# NE556-CD4069-Synth-Toy-CableConn.net
KiCad netlist of a schematic drawn in EAGLE
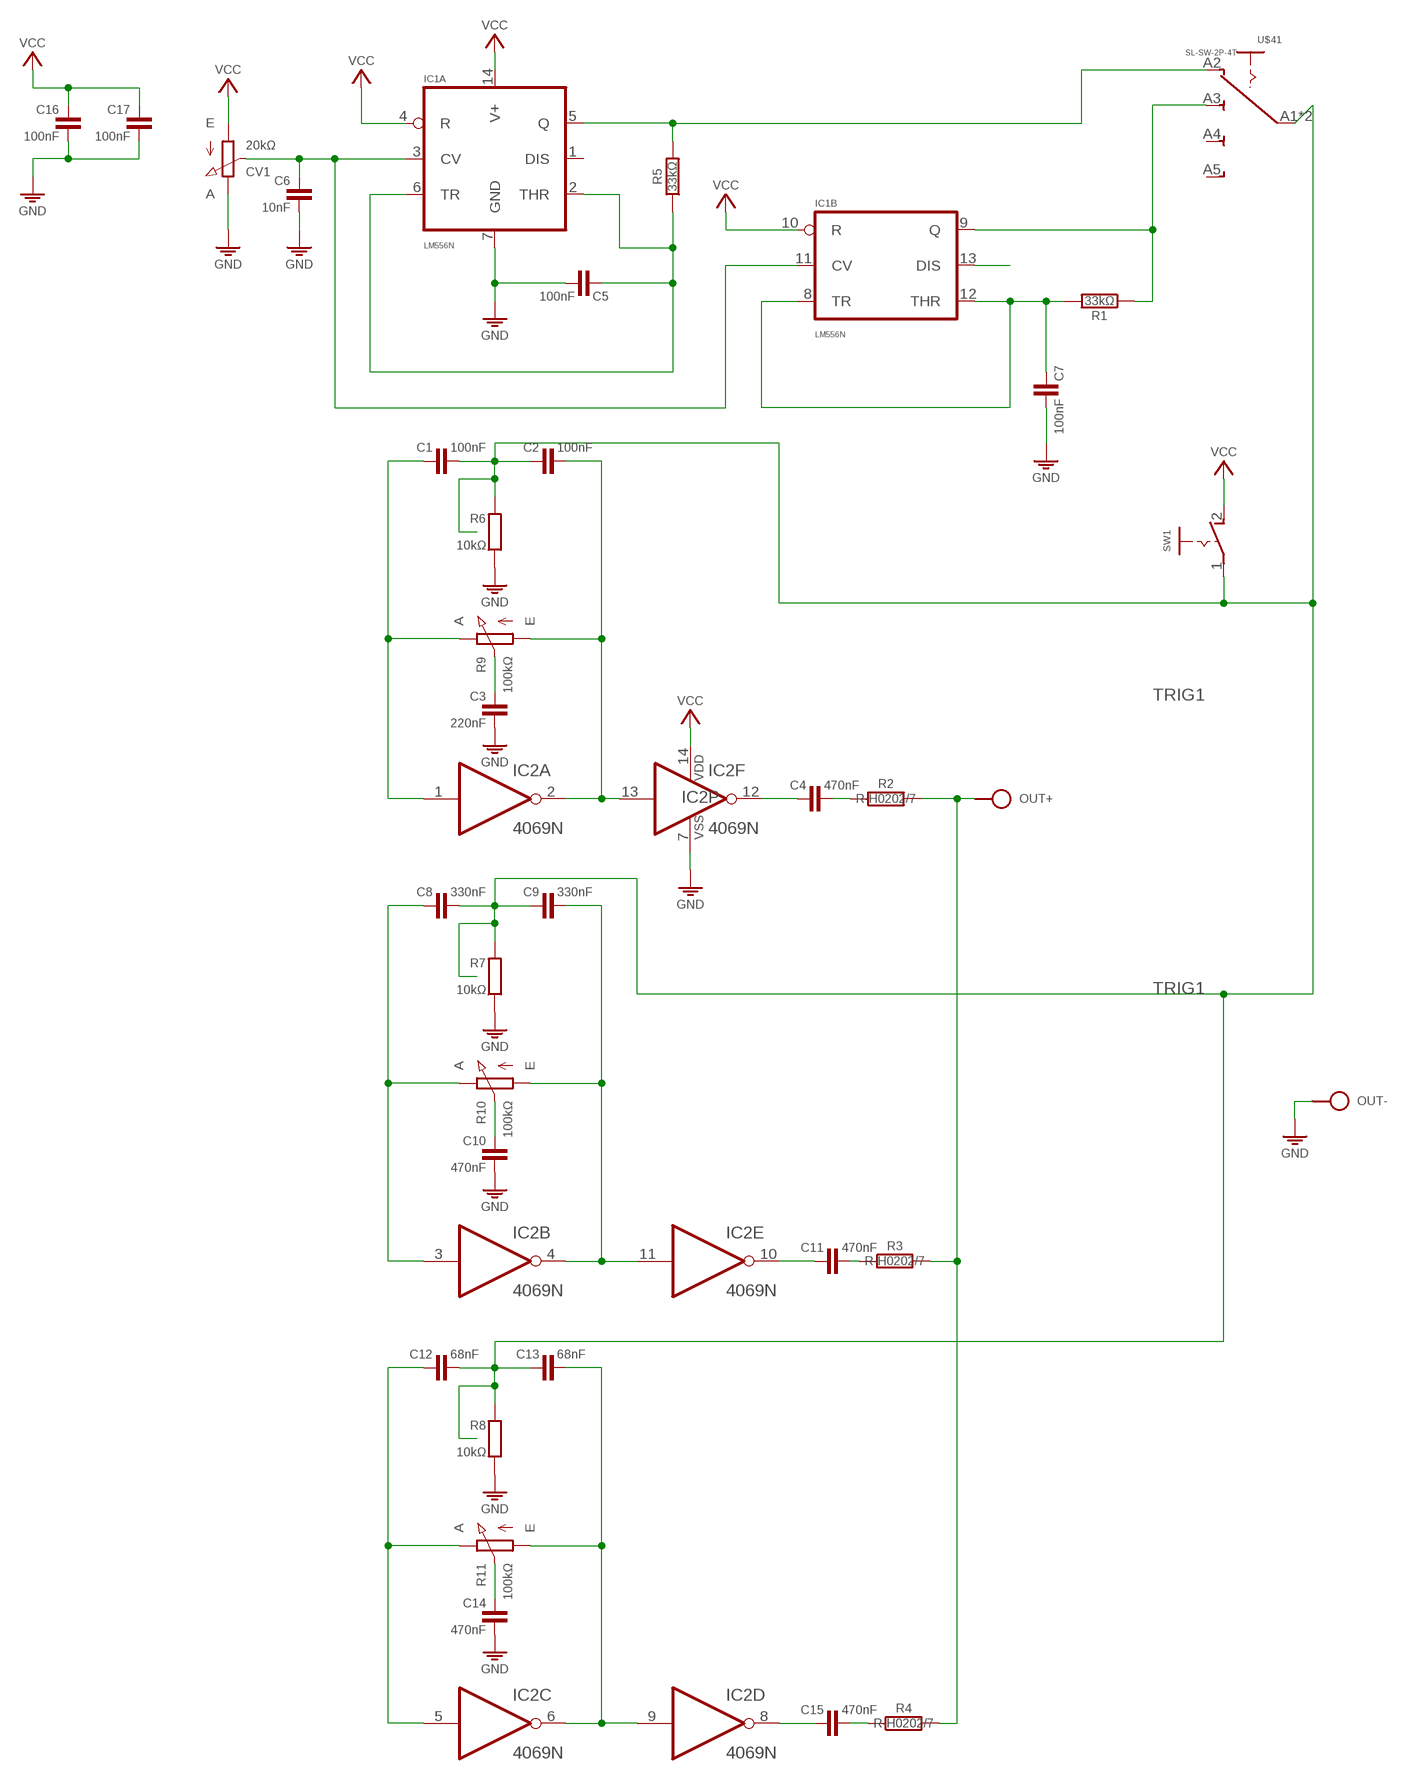
[diagram p0: schematic, sheet 1]

(export (version "E")
  (design (tool "Eeschema 10.0.6"))
  (components
    (comp (ref "C1")
      (value "100nF")
      (footprint "eagle-import:C050-020X044")
      (libsource (lib "eagle-import") (part "C-H050-020X044"))
    )
    (comp (ref "C2")
      (value "100nF")
      (footprint "eagle-import:C050-020X044")
      (libsource (lib "eagle-import") (part "C-H050-020X044"))
    )
    (comp (ref "C3")
      (value "220nF")
      (footprint "eagle-import:C050-020X044_V")
      (libsource (lib "eagle-import") (part "C050-020X044/V"))
    )
    (comp (ref "C4")
      (value "470nF")
      (footprint "eagle-import:C050-024X044")
      (libsource (lib "eagle-import") (part "C-H050-024X044"))
    )
    (comp (ref "C5")
      (value "100nF")
      (footprint "eagle-import:C050-020X044")
      (libsource (lib "eagle-import") (part "C-H050-020X044"))
    )
    (comp (ref "C6")
      (value "10nF")
      (footprint "eagle-import:C050-020X044_V")
      (libsource (lib "eagle-import") (part "C050-020X044/V"))
    )
    (comp (ref "C7")
      (value "100nF")
      (footprint "eagle-import:C050-020X044")
      (libsource (lib "eagle-import") (part "C-H050-020X044"))
    )
    (comp (ref "C8")
      (value "330nF")
      (footprint "eagle-import:C050-024X044")
      (libsource (lib "eagle-import") (part "C-H050-024X044"))
    )
    (comp (ref "C9")
      (value "330nF")
      (footprint "eagle-import:C050-024X044")
      (libsource (lib "eagle-import") (part "C-H050-024X044"))
    )
    (comp (ref "C10")
      (value "470nF")
      (footprint "eagle-import:C050-020X044_V")
      (libsource (lib "eagle-import") (part "C050-020X044/V"))
    )
    (comp (ref "C11")
      (value "470nF")
      (footprint "eagle-import:C050-024X044")
      (libsource (lib "eagle-import") (part "C-H050-024X044"))
    )
    (comp (ref "C12")
      (value "68nF")
      (footprint "eagle-import:C050-020X044")
      (libsource (lib "eagle-import") (part "C-H050-020X044"))
    )
    (comp (ref "C13")
      (value "68nF")
      (footprint "eagle-import:C050-020X044")
      (libsource (lib "eagle-import") (part "C-H050-020X044"))
    )
    (comp (ref "C14")
      (value "470nF")
      (footprint "eagle-import:C050-020X044_V")
      (libsource (lib "eagle-import") (part "C050-020X044/V"))
    )
    (comp (ref "C15")
      (value "470nF")
      (footprint "eagle-import:C050-024X044")
      (libsource (lib "eagle-import") (part "C-H050-024X044"))
    )
    (comp (ref "C16")
      (value "100nF")
      (footprint "eagle-import:C050-020X044_V")
      (libsource (lib "eagle-import") (part "C050-020X044/V"))
    )
    (comp (ref "C17")
      (value "100nF")
      (footprint "eagle-import:C050-020X044_V")
      (libsource (lib "eagle-import") (part "C050-020X044/V"))
    )
    (comp (ref "CV1")
      (value "20kΩ")
      (footprint "eagle-import:CONN-3P")
      (libsource (lib "eagle-import") (part "POT-3P"))
    )
    (comp (ref "IC1")
      (value "LM556N")
      (footprint "eagle-import:DIL14")
      (libsource (lib "eagle-import") (part "556NLM"))
    )
    (comp (ref "IC2")
      (value "4069N")
      (footprint "eagle-import:DIL14")
      (libsource (lib "eagle-import") (part "4069N"))
    )
    (comp (ref "OUT")
      (value "SPAD+--+")
      (footprint "eagle-import:SPAD-+")
      (libsource (lib "eagle-import") (part "SPAD+--+"))
    )
    (comp (ref "R1")
      (value "33kΩ")
      (footprint "eagle-import:0204_2V")
      (libsource (lib "eagle-import") (part "R-H0204/2V"))
    )
    (comp (ref "R2")
      (value "R-H0202/7")
      (footprint "eagle-import:0202_7")
      (libsource (lib "eagle-import") (part "R-H0202/7"))
    )
    (comp (ref "R3")
      (value "R-H0202/7")
      (footprint "eagle-import:0202_7")
      (libsource (lib "eagle-import") (part "R-H0202/7"))
    )
    (comp (ref "R4")
      (value "R-H0202/7")
      (footprint "eagle-import:0202_7")
      (libsource (lib "eagle-import") (part "R-H0202/7"))
    )
    (comp (ref "R5")
      (value "33kΩ")
      (footprint "eagle-import:0204_2V")
      (libsource (lib "eagle-import") (part "R-H0204/2V"))
    )
    (comp (ref "R6")
      (value "10kΩ")
      (footprint "eagle-import:0204_10-V")
      (libsource (lib "eagle-import") (part "R0204/10-V"))
    )
    (comp (ref "R7")
      (value "10kΩ")
      (footprint "eagle-import:0204_10-V")
      (libsource (lib "eagle-import") (part "R0204/10-V"))
    )
    (comp (ref "R8")
      (value "10kΩ")
      (footprint "eagle-import:0204_10-V")
      (libsource (lib "eagle-import") (part "R0204/10-V"))
    )
    (comp (ref "R9")
      (value "100kΩ")
      (footprint "eagle-import:CONN-3P")
      (libsource (lib "eagle-import") (part "POT-3P-S1"))
    )
    (comp (ref "R10")
      (value "100kΩ")
      (footprint "eagle-import:CONN-3P")
      (libsource (lib "eagle-import") (part "POT-3P-S1"))
    )
    (comp (ref "R11")
      (value "100kΩ")
      (footprint "eagle-import:CONN-3P")
      (libsource (lib "eagle-import") (part "POT-3P-S1"))
    )
    (comp (ref "S3")
      (value "VCC_GNDPWR-L")
      (footprint "eagle-import:PWR-L")
      (libsource (lib "eagle-import") (part "VCC_GNDPWR-L"))
    )
    (comp (ref "SW1")
      (value "PB-1P-1T")
      (footprint "eagle-import:PB-1P1T")
      (libsource (lib "eagle-import") (part "PB-1P-1T"))
    )
    (comp (ref "U$4")
      (value "SL-SW-2P-4T")
      (footprint "eagle-import:SLSW-2P4T-2-H")
      (libsource (lib "eagle-import") (part "SL-SW-2P-4T"))
    )
  )
  (nets
    (net (code "1") (name "/TRIG1") (class "Default")
      (node (ref "C1") (pin "2") (pinfunction "2_2") (pintype "passive"))
      (node (ref "C12") (pin "2") (pinfunction "2_2") (pintype "passive"))
      (node (ref "C13") (pin "1") (pinfunction "1_1") (pintype "passive"))
      (node (ref "C2") (pin "1") (pinfunction "1_1") (pintype "passive"))
      (node (ref "C8") (pin "2") (pinfunction "2_2") (pintype "passive"))
      (node (ref "C9") (pin "1") (pinfunction "1_1") (pintype "passive"))
      (node (ref "R6") (pin "1") (pinfunction "1_1") (pintype "passive"))
      (node (ref "R7") (pin "1") (pinfunction "1_1") (pintype "passive"))
      (node (ref "R8") (pin "1") (pinfunction "1_1") (pintype "passive"))
      (node (ref "SW1") (pin "1") (pinfunction "P_1") (pintype "passive"))
      (node (ref "U$4") (pin "A1") (pinfunction "P_A1") (pintype "passive"))
      (node (ref "U$4") (pin "A6") (pinfunction "P_A6") (pintype "passive"))
    )
    (net (code "2") (name "GND") (class "Default")
      (node (ref "C10") (pin "2") (pinfunction "2_2") (pintype "passive"))
      (node (ref "C14") (pin "2") (pinfunction "2_2") (pintype "passive"))
      (node (ref "C16") (pin "2") (pinfunction "2_2") (pintype "passive"))
      (node (ref "C17") (pin "2") (pinfunction "2_2") (pintype "passive"))
      (node (ref "C3") (pin "2") (pinfunction "2_2") (pintype "passive"))
      (node (ref "C5") (pin "2") (pinfunction "2_2") (pintype "passive"))
      (node (ref "C6") (pin "2") (pinfunction "2_2") (pintype "passive"))
      (node (ref "C7") (pin "2") (pinfunction "2_2") (pintype "passive"))
      (node (ref "CV1") (pin "3") (pinfunction "E_3") (pintype "passive"))
      (node (ref "IC1") (pin "7") (pinfunction "GND_7") (pintype "power_in"))
      (node (ref "IC2") (pin "7") (pinfunction "VSS_7") (pintype "power_in"))
      (node (ref "OUT") (pin "1") (pinfunction "P$1_1") (pintype "passive"))
      (node (ref "R6") (pin "2") (pinfunction "2_2") (pintype "passive"))
      (node (ref "R7") (pin "2") (pinfunction "2_2") (pintype "passive"))
      (node (ref "R8") (pin "2") (pinfunction "2_2") (pintype "passive"))
      (node (ref "S3") (pin "1") (pinfunction "GND_1") (pintype "power_in"))
    )
    (net (code "3") (name "Net-(C4-Pad2)") (class "Default")
      (node (ref "C4") (pin "2") (pinfunction "2_2") (pintype "passive"))
      (node (ref "R2") (pin "1") (pinfunction "1_1") (pintype "passive"))
    )
    (net (code "4") (name "Net-(C11-Pad2)") (class "Default")
      (node (ref "C11") (pin "2") (pinfunction "2_2") (pintype "passive"))
      (node (ref "R3") (pin "1") (pinfunction "1_1") (pintype "passive"))
    )
    (net (code "5") (name "Net-(C15-Pad2)") (class "Default")
      (node (ref "C15") (pin "2") (pinfunction "2_2") (pintype "passive"))
      (node (ref "R4") (pin "1") (pinfunction "1_1") (pintype "passive"))
    )
    (net (code "6") (name "Net-(CV1-S)") (class "Default")
      (node (ref "C6") (pin "1") (pinfunction "1_1") (pintype "passive"))
      (node (ref "CV1") (pin "2") (pinfunction "S_2") (pintype "passive"))
      (node (ref "IC1") (pin "11") (pinfunction "CV_11") (pintype "input"))
      (node (ref "IC1") (pin "3") (pinfunction "CV_3") (pintype "input"))
    )
    (net (code "7") (name "Net-(IC1A-Q)") (class "Default")
      (node (ref "IC1") (pin "5") (pinfunction "Q_5") (pintype "output"))
      (node (ref "R5") (pin "2") (pinfunction "2_2") (pintype "passive"))
      (node (ref "U$4") (pin "A2") (pinfunction "A_A2") (pintype "passive"))
    )
    (net (code "8") (name "Net-(IC1A-THR)") (class "Default")
      (node (ref "C5") (pin "1") (pinfunction "1_1") (pintype "passive"))
      (node (ref "IC1") (pin "2") (pinfunction "THR_2") (pintype "input"))
      (node (ref "IC1") (pin "6") (pinfunction "TR_6") (pintype "input"))
      (node (ref "R5") (pin "1") (pinfunction "1_1") (pintype "passive"))
    )
    (net (code "9") (name "Net-(IC1B-Q)") (class "Default")
      (node (ref "IC1") (pin "9") (pinfunction "Q_9") (pintype "output"))
      (node (ref "R1") (pin "1") (pinfunction "1_1") (pintype "passive"))
      (node (ref "U$4") (pin "A3") (pinfunction "B_A3") (pintype "passive"))
    )
    (net (code "10") (name "Net-(IC1B-THR)") (class "Default")
      (node (ref "C7") (pin "1") (pinfunction "1_1") (pintype "passive"))
      (node (ref "IC1") (pin "12") (pinfunction "THR_12") (pintype "input"))
      (node (ref "IC1") (pin "8") (pinfunction "TR_8") (pintype "input"))
      (node (ref "R1") (pin "2") (pinfunction "2_2") (pintype "passive"))
    )
    (net (code "11") (name "Net-(IC2A-I)") (class "Default")
      (node (ref "C1") (pin "1") (pinfunction "1_1") (pintype "passive"))
      (node (ref "IC2") (pin "1") (pinfunction "I_1") (pintype "input"))
      (node (ref "R9") (pin "3") (pinfunction "E_3") (pintype "passive"))
    )
    (net (code "12") (name "Net-(IC2A-O)") (class "Default")
      (node (ref "C2") (pin "2") (pinfunction "2_2") (pintype "passive"))
      (node (ref "IC2") (pin "13") (pinfunction "I_13") (pintype "input"))
      (node (ref "IC2") (pin "2") (pinfunction "O_2") (pintype "output"))
      (node (ref "R9") (pin "2") (pinfunction "A_2") (pintype "passive"))
    )
    (net (code "13") (name "Net-(IC2B-I)") (class "Default")
      (node (ref "C8") (pin "1") (pinfunction "1_1") (pintype "passive"))
      (node (ref "IC2") (pin "3") (pinfunction "I_3") (pintype "input"))
      (node (ref "R10") (pin "3") (pinfunction "E_3") (pintype "passive"))
    )
    (net (code "14") (name "Net-(IC2B-O)") (class "Default")
      (node (ref "C9") (pin "2") (pinfunction "2_2") (pintype "passive"))
      (node (ref "IC2") (pin "11") (pinfunction "I_11") (pintype "input"))
      (node (ref "IC2") (pin "4") (pinfunction "O_4") (pintype "output"))
      (node (ref "R10") (pin "2") (pinfunction "A_2") (pintype "passive"))
    )
    (net (code "15") (name "Net-(IC2C-I)") (class "Default")
      (node (ref "C12") (pin "1") (pinfunction "1_1") (pintype "passive"))
      (node (ref "IC2") (pin "5") (pinfunction "I_5") (pintype "input"))
      (node (ref "R11") (pin "3") (pinfunction "E_3") (pintype "passive"))
    )
    (net (code "16") (name "Net-(IC2C-O)") (class "Default")
      (node (ref "C13") (pin "2") (pinfunction "2_2") (pintype "passive"))
      (node (ref "IC2") (pin "6") (pinfunction "O_6") (pintype "output"))
      (node (ref "IC2") (pin "9") (pinfunction "I_9") (pintype "input"))
      (node (ref "R11") (pin "2") (pinfunction "A_2") (pintype "passive"))
    )
    (net (code "17") (name "Net-(IC2D-O)") (class "Default")
      (node (ref "C15") (pin "1") (pinfunction "1_1") (pintype "passive"))
      (node (ref "IC2") (pin "8") (pinfunction "O_8") (pintype "output"))
    )
    (net (code "18") (name "Net-(IC2E-O)") (class "Default")
      (node (ref "C11") (pin "1") (pinfunction "1_1") (pintype "passive"))
      (node (ref "IC2") (pin "10") (pinfunction "O_10") (pintype "output"))
    )
    (net (code "19") (name "Net-(IC2F-O)") (class "Default")
      (node (ref "C4") (pin "1") (pinfunction "1_1") (pintype "passive"))
      (node (ref "IC2") (pin "12") (pinfunction "O_12") (pintype "output"))
    )
    (net (code "20") (name "Net-(OUTA-P$1)") (class "Default")
      (node (ref "OUT") (pin "2") (pinfunction "P$1_2") (pintype "passive"))
      (node (ref "R2") (pin "2") (pinfunction "2_2") (pintype "passive"))
      (node (ref "R3") (pin "2") (pinfunction "2_2") (pintype "passive"))
      (node (ref "R4") (pin "2") (pinfunction "2_2") (pintype "passive"))
    )
    (net (code "21") (name "Net-(R9-S)") (class "Default")
      (node (ref "C3") (pin "1") (pinfunction "1_1") (pintype "passive"))
      (node (ref "R9") (pin "1") (pinfunction "S_1") (pintype "passive"))
    )
    (net (code "22") (name "Net-(R10-S)") (class "Default")
      (node (ref "C10") (pin "1") (pinfunction "1_1") (pintype "passive"))
      (node (ref "R10") (pin "1") (pinfunction "S_1") (pintype "passive"))
    )
    (net (code "23") (name "Net-(R11-S)") (class "Default")
      (node (ref "C14") (pin "1") (pinfunction "1_1") (pintype "passive"))
      (node (ref "R11") (pin "1") (pinfunction "S_1") (pintype "passive"))
    )
    (net (code "24") (name "VCC") (class "Default")
      (node (ref "C16") (pin "1") (pinfunction "1_1") (pintype "passive"))
      (node (ref "C17") (pin "1") (pinfunction "1_1") (pintype "passive"))
      (node (ref "CV1") (pin "1") (pinfunction "A_1") (pintype "passive"))
      (node (ref "IC1") (pin "10") (pinfunction "R_10") (pintype "input"))
      (node (ref "IC1") (pin "14") (pinfunction "V+_14") (pintype "power_in"))
      (node (ref "IC1") (pin "4") (pinfunction "R_4") (pintype "input"))
      (node (ref "IC2") (pin "14") (pinfunction "VDD_14") (pintype "power_in"))
      (node (ref "S3") (pin "2") (pinfunction "VCC_2") (pintype "power_in"))
      (node (ref "SW1") (pin "2") (pinfunction "S_2") (pintype "passive"))
    )
    (net (code "25") (name "unconnected-(IC1A-DIS-Pad1)") (class "Default")
      (node (ref "IC1") (pin "1") (pinfunction "DIS_1") (pintype "passive"))
    )
    (net (code "26") (name "unconnected-(IC1B-DIS-Pad13)") (class "Default")
      (node (ref "IC1") (pin "13") (pinfunction "DIS_13") (pintype "input"))
    )
    (net (code "27") (name "unconnected-(U$4A-C-PadA4)") (class "Default")
      (node (ref "U$4") (pin "A4") (pinfunction "C_A4") (pintype "passive"))
    )
    (net (code "28") (name "unconnected-(U$4A-D-PadA5)") (class "Default")
      (node (ref "U$4") (pin "A5") (pinfunction "D_A5") (pintype "passive"))
    )
  )
)
